# SCH_schematicCardPCB_2024-03-03.net
KiCad netlist of a schematic drawn in EasyEDA
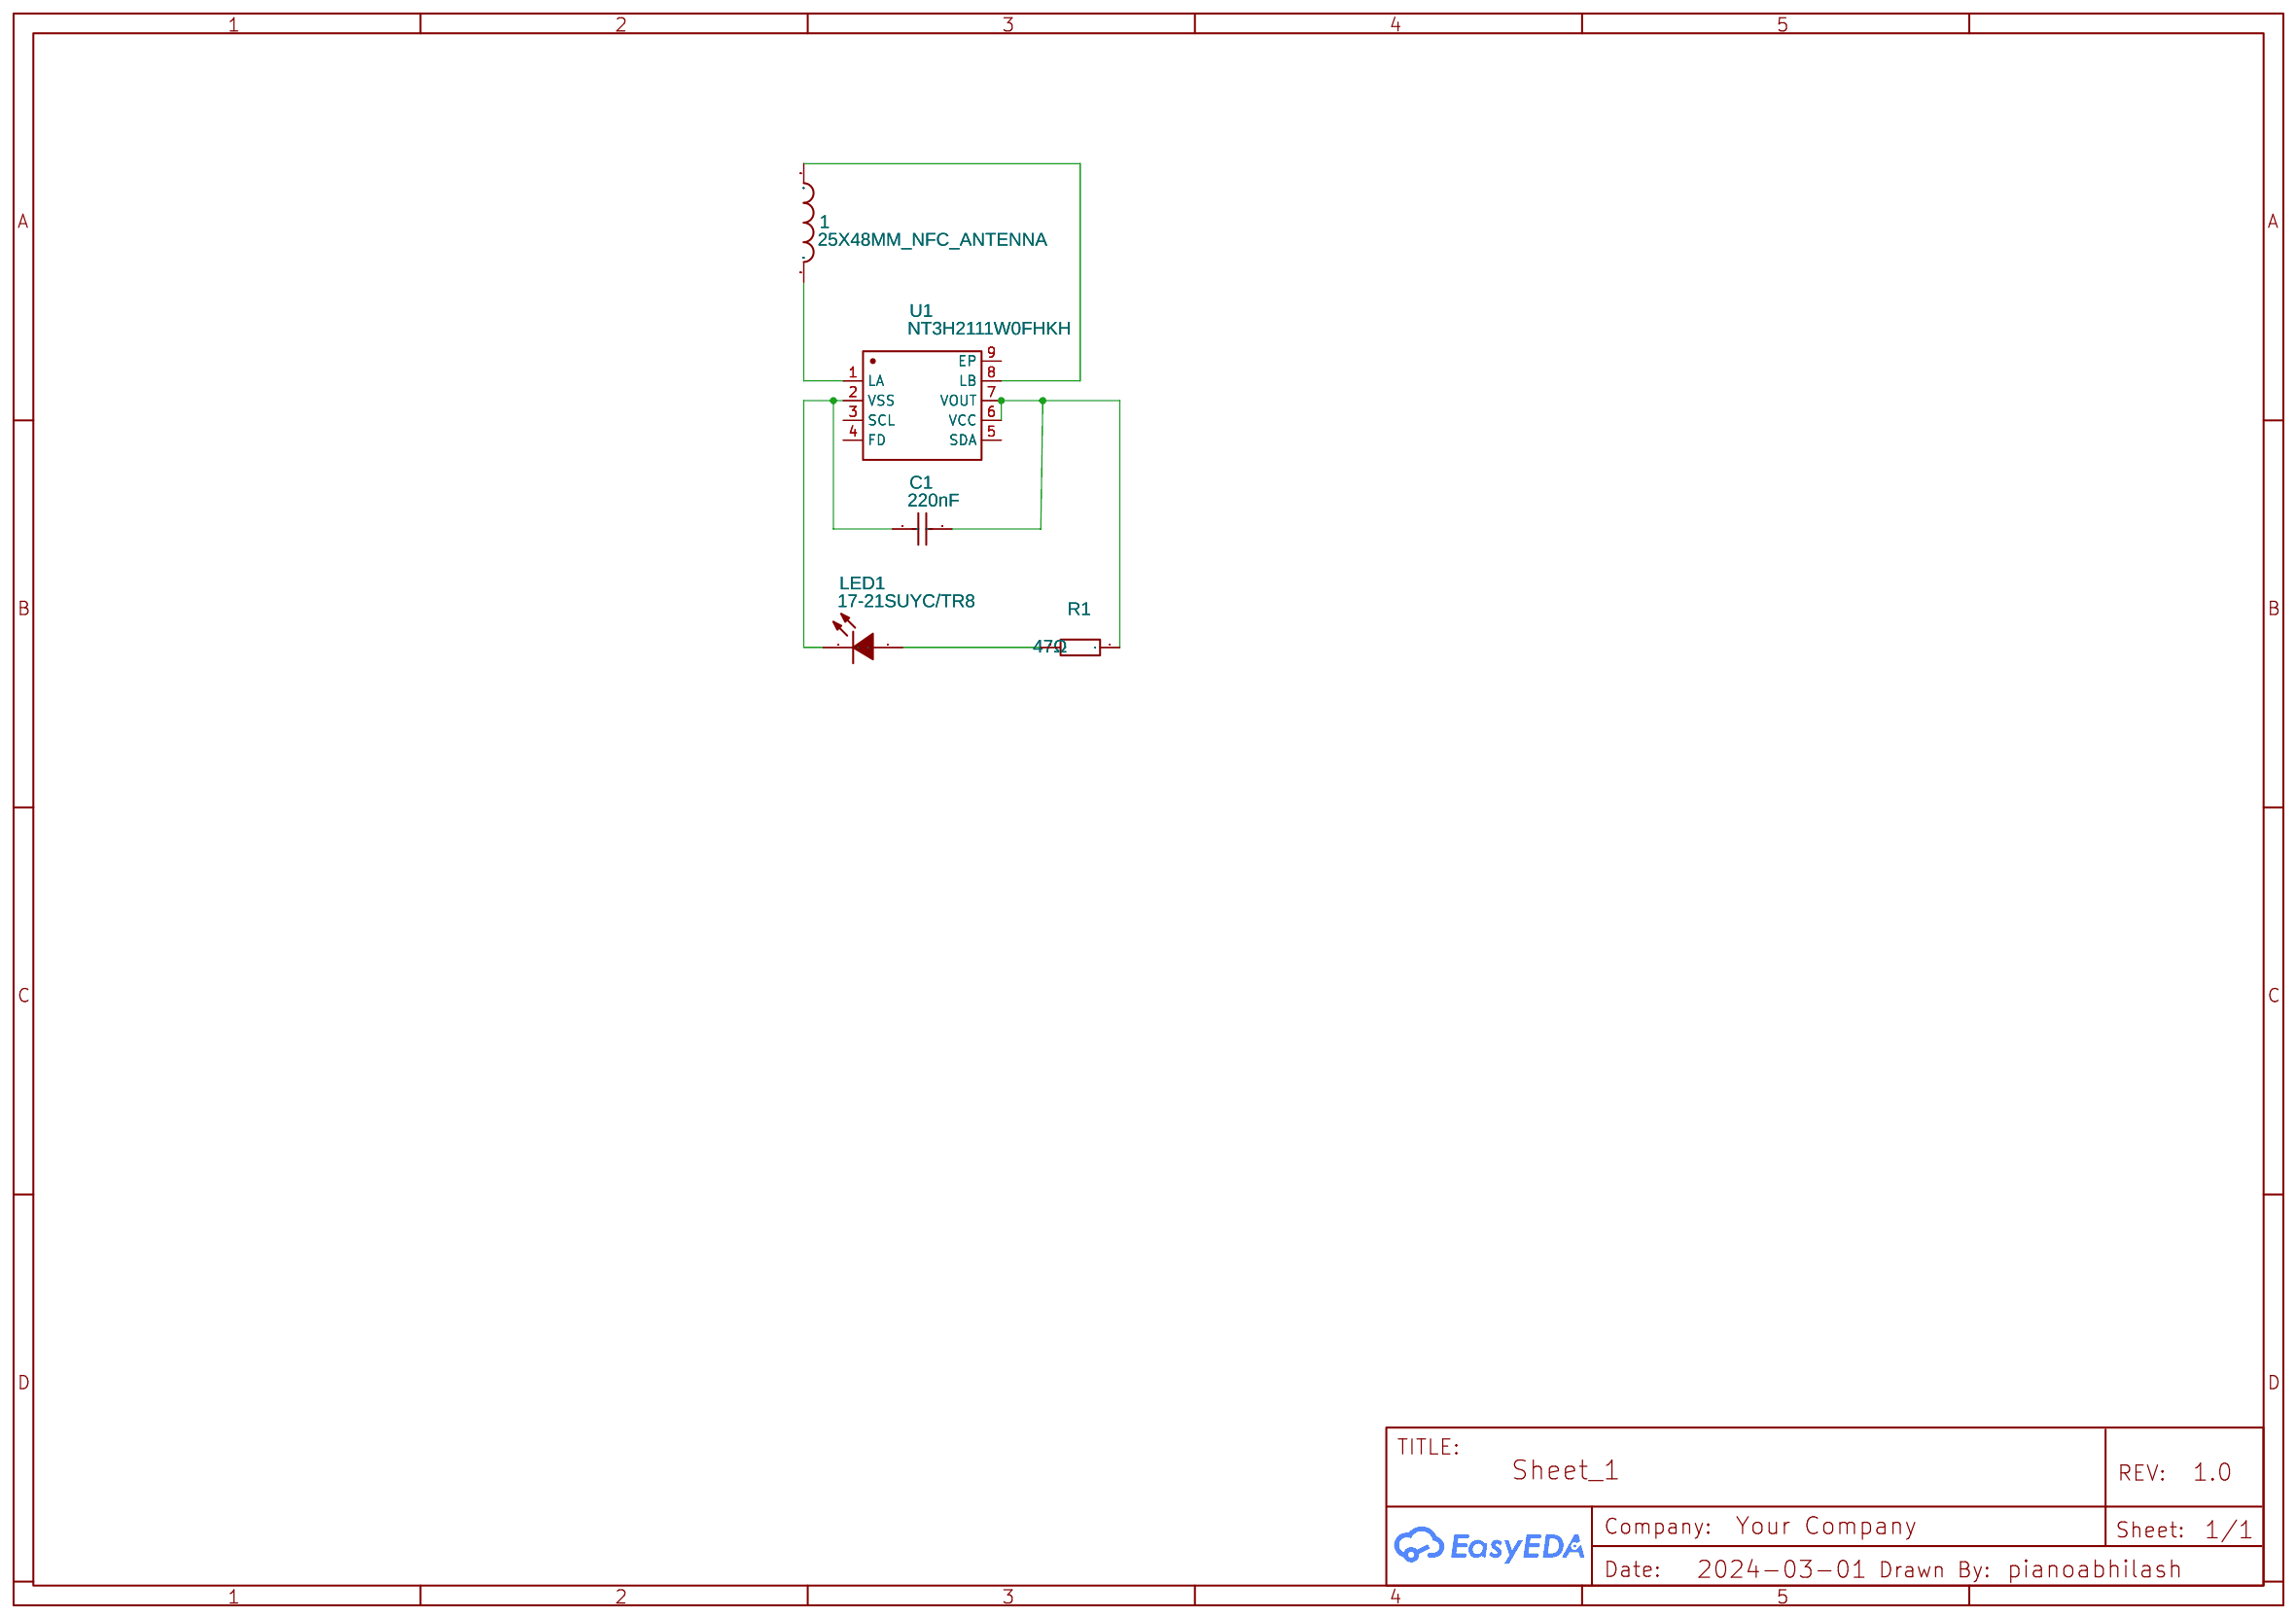
[diagram p0: schematic sheet]

(export (version "E")
  (design (tool "Eeschema 10.0.6"))
  (components
    (comp (ref "1") (value "25X48MM_NFC_ANTENNA") (libsource (lib "") (part "25X48MM_NFC_ANTENNA")))
    (comp (ref "C1")
      (value "220nF")
      (fields
        (field (name "Manufacturer Part") "CL10B224KA8NNNC")
        (field (name "Manufacturer") "SAMSUNG(三星)")
      )
      (libsource (lib "") (part "CL10B224KA8NNNC"))
    )
    (comp (ref "LED1")
      (value "17-21SUYC/TR8")
      (fields (field (name "Manufacturer Part") "KT-0805黄灯") (field (name "Manufacturer") "KENTO"))
      (libsource (lib "") (part "17-21SUYC/TR8"))
    )
    (comp (ref "R1")
      (value "47Ω")
      (fields
        (field (name "Manufacturer Part") "0603WAF470JT5E")
        (field (name "Manufacturer") "UNI-ROYAL(厚声)")
      )
      (libsource (lib "") (part "0603WAF470JT5E"))
    )
    (comp (ref "U1")
      (value "NT3H2111W0FHKH")
      (fields (field (name "Manufacturer") "NXP(恩智浦)"))
      (libsource (lib "") (part "NT3H2111W0FHKH"))
    )
  )
  (nets
    (net (code "1") (name "Net-(LED1-+)") (class "Default")
      (node (ref "LED1") (pin "1") (pinfunction "+_1") (pintype "unspecified"))
      (node (ref "R1") (pin "1") (pinfunction "1_1") (pintype "input"))
    )
    (net (code "2") (name "Net-(LED1--)") (class "Default")
      (node (ref "C1") (pin "1") (pinfunction "1_1") (pintype "input"))
      (node (ref "LED1") (pin "2") (pinfunction "-_2") (pintype "unspecified"))
      (node (ref "U1") (pin "2") (pinfunction "VSS_2") (pintype "unspecified"))
    )
    (net (code "3") (name "Net-(U1-LA)") (class "Default")
      (node (ref "1") (pin "P$2") (pinfunction "P$2_P$2") (pintype "bidirectional"))
      (node (ref "U1") (pin "1") (pinfunction "LA_1") (pintype "unspecified"))
    )
    (net (code "4") (name "Net-(U1-LB)") (class "Default")
      (node (ref "1") (pin "P$1") (pinfunction "P$1_P$1") (pintype "bidirectional"))
      (node (ref "U1") (pin "8") (pinfunction "LB_8") (pintype "unspecified"))
    )
    (net (code "5") (name "Net-(U1-VCC)") (class "Default")
      (node (ref "C1") (pin "2") (pinfunction "2_2") (pintype "input"))
      (node (ref "R1") (pin "2") (pinfunction "2_2") (pintype "input"))
      (node (ref "U1") (pin "6") (pinfunction "VCC_6") (pintype "unspecified"))
      (node (ref "U1") (pin "7") (pinfunction "VOUT_7") (pintype "unspecified"))
    )
    (net (code "6") (name "unconnected-(U1-EP-Pad9)") (class "Default")
      (node (ref "U1") (pin "9") (pinfunction "EP_9") (pintype "unspecified"))
    )
    (net (code "7") (name "unconnected-(U1-FD-Pad4)") (class "Default")
      (node (ref "U1") (pin "4") (pinfunction "FD_4") (pintype "unspecified"))
    )
    (net (code "8") (name "unconnected-(U1-SCL-Pad3)") (class "Default")
      (node (ref "U1") (pin "3") (pinfunction "SCL_3") (pintype "unspecified"))
    )
    (net (code "9") (name "unconnected-(U1-SDA-Pad5)") (class "Default")
      (node (ref "U1") (pin "5") (pinfunction "SDA_5") (pintype "unspecified"))
    )
  )
)
